# T1_Data_Top_Level.net
KiCad netlist of a schematic drawn in Altium Designer
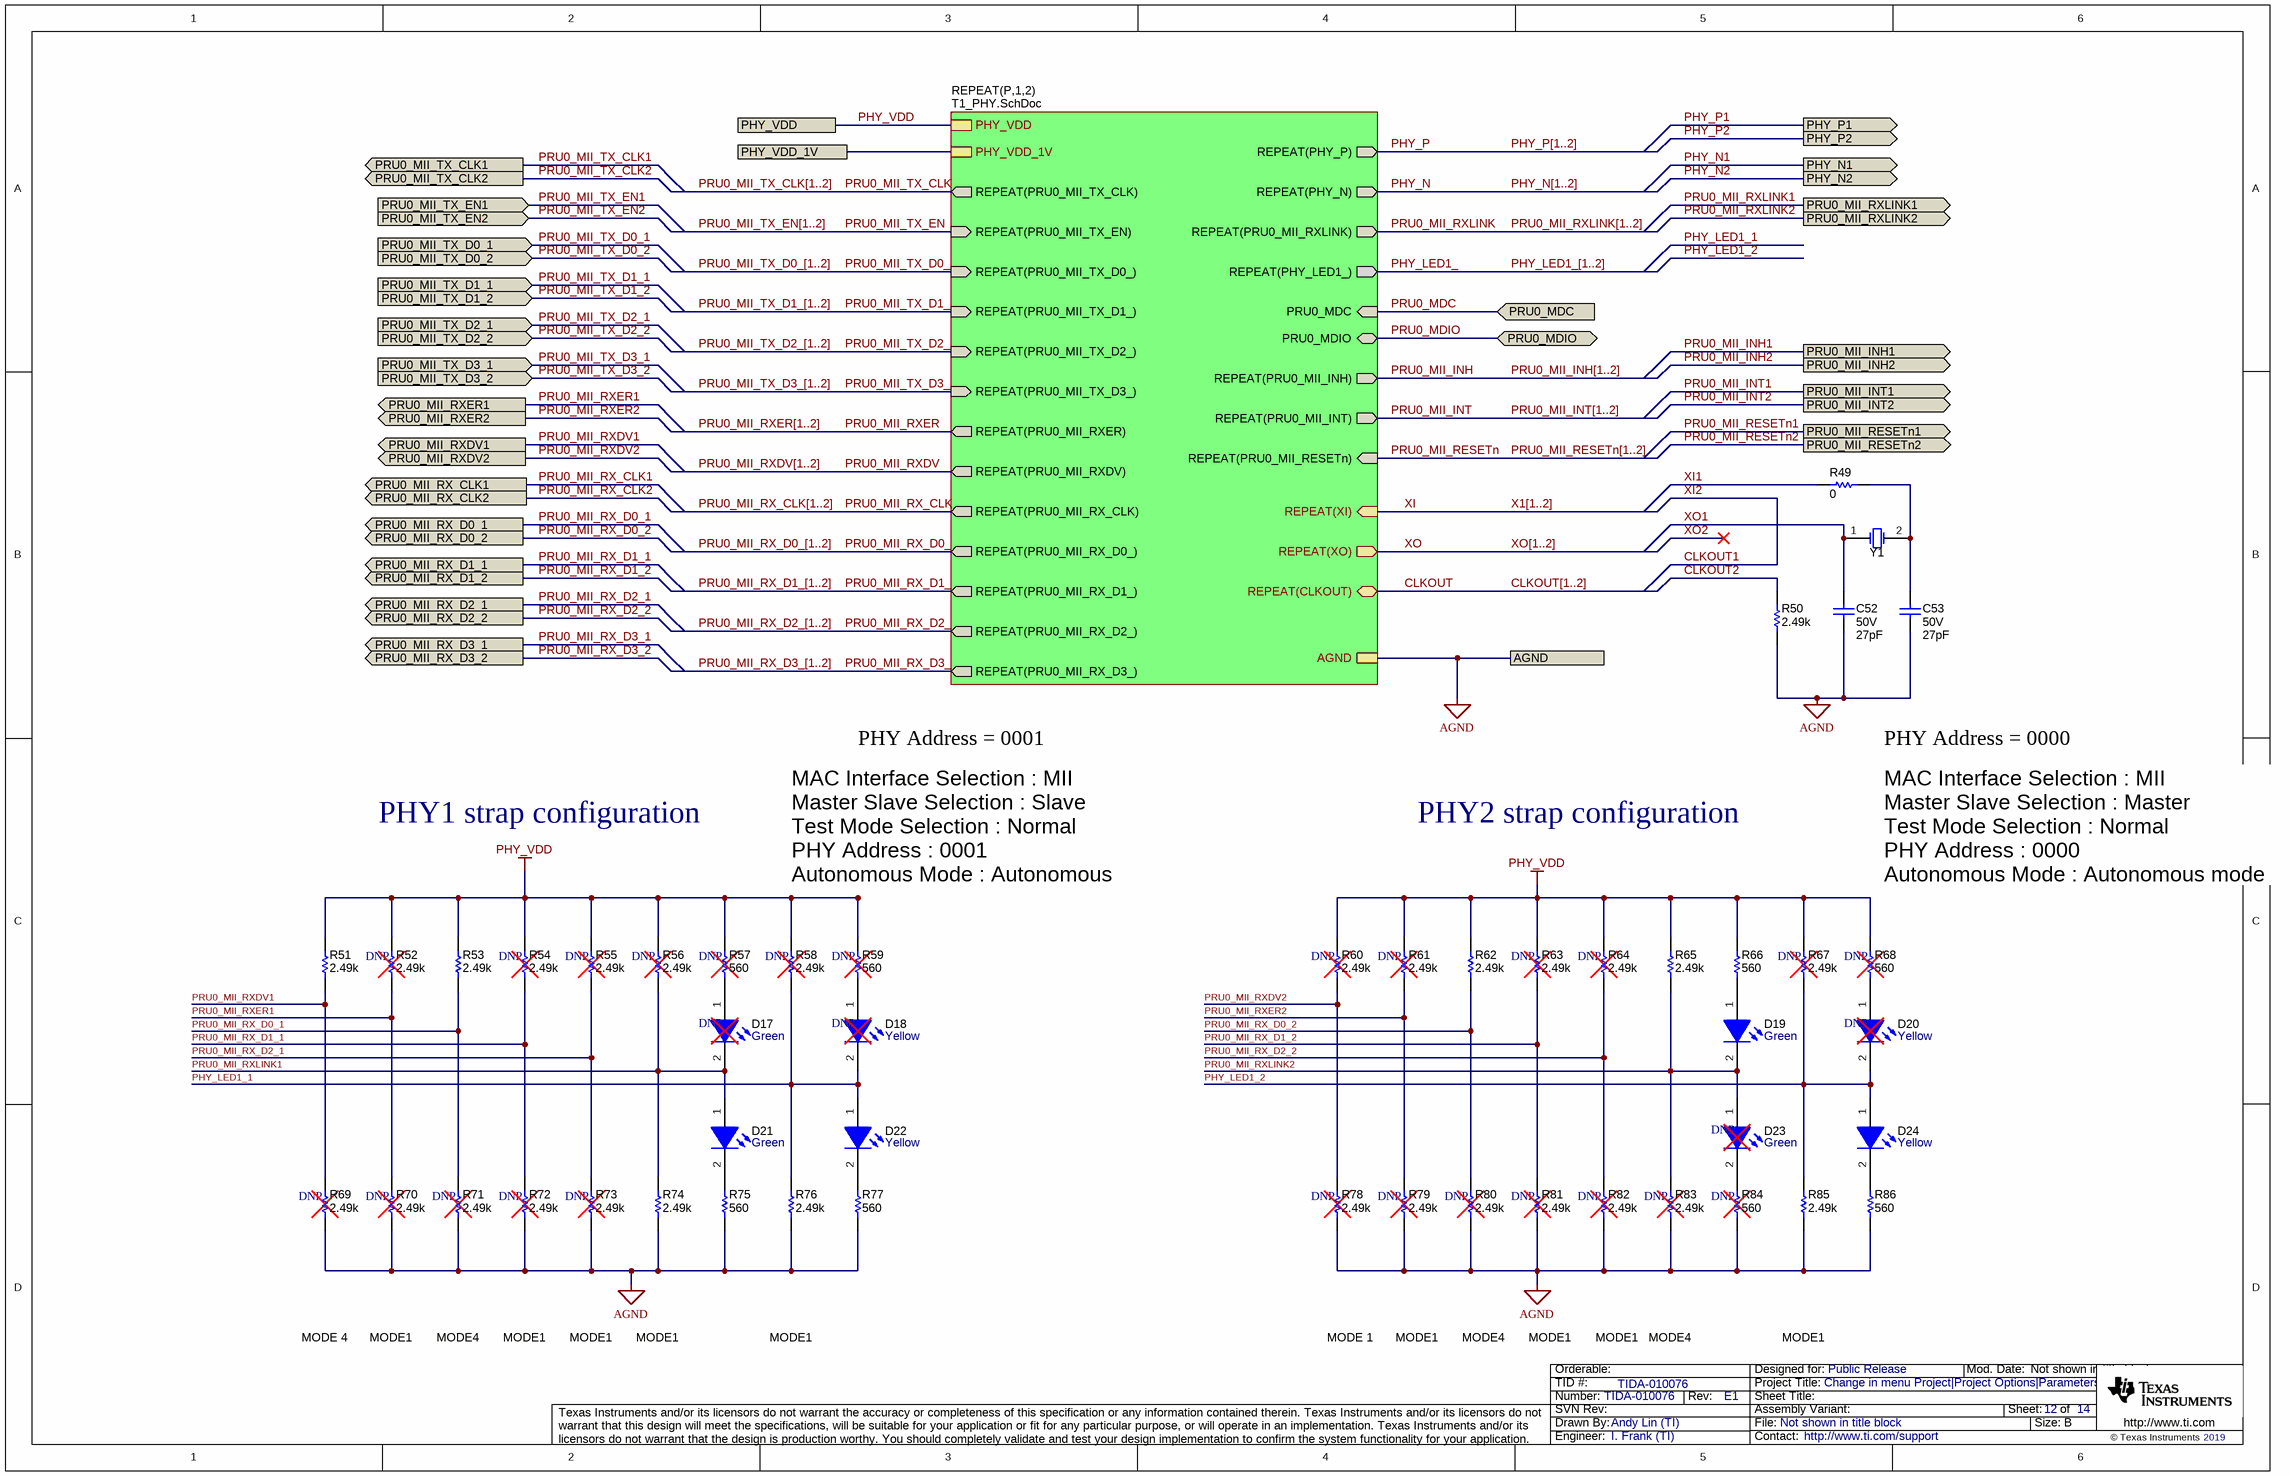
[diagram p0: T1_Data_Top_Level.SchDoc]

(export (version "E")
  (design (tool "Eeschema 10.0.6"))
  (components
    (comp (ref "C52")
      (value "GRM1885C1H270JA01D")
      (footprint "0603")
      (description "CAP, CERM, 27 pF, 50 V, +/- 5%, C0G/NP0, 0603")
      (fields
        (field (name "MANUFACTURER") "MuRata")
        (field (name "VDC_V") "50V")
        (field (name "VALUEDISPLAYED") "27pF")
        (field (name "PUBLISHER") "Texas Instruments")
      )
      (libsource (lib "Altium Vault - TI") (part "Capacitor"))
    )
    (comp (ref "C53")
      (value "GRM1885C1H270JA01D")
      (footprint "0603")
      (description "CAP, CERM, 27 pF, 50 V, +/- 5%, C0G/NP0, 0603")
      (fields
        (field (name "MANUFACTURER") "MuRata")
        (field (name "VDC_V") "50V")
        (field (name "VALUEDISPLAYED") "27pF")
        (field (name "PUBLISHER") "Texas Instruments")
      )
      (libsource (lib "Altium Vault - TI") (part "Capacitor"))
    )
    (comp (ref "D17")
      (value "Green")
      (footprint "LG L29K_GREEN")
      (description "LED, Green, SMD")
      (fields (field (name "MANUFACTURER") "OSRAM") (field (name "PARTNUMBER") "LG L29K-G2J1-24-Z"))
      (libsource (lib "Altium Vault - TI") (part "LED"))
    )
    (comp (ref "D18")
      (value "Yellow")
      (footprint "LY L29K_Yellow")
      (description "LED, Yellow, SMD")
      (fields (field (name "PARTNUMBER") "LY L29K-J1K2-26-Z") (field (name "MANUFACTURER") "OSRAM"))
      (libsource (lib "Altium Vault - TI") (part "LED"))
    )
    (comp (ref "D19")
      (value "Green")
      (footprint "LG L29K_GREEN")
      (description "LED, Green, SMD")
      (fields (field (name "MANUFACTURER") "OSRAM") (field (name "PARTNUMBER") "LG L29K-G2J1-24-Z"))
      (libsource (lib "Altium Vault - TI") (part "LED"))
    )
    (comp (ref "D20")
      (value "Yellow")
      (footprint "LY L29K_Yellow")
      (description "LED, Yellow, SMD")
      (fields (field (name "PARTNUMBER") "LY L29K-J1K2-26-Z") (field (name "MANUFACTURER") "OSRAM"))
      (libsource (lib "Altium Vault - TI") (part "LED"))
    )
    (comp (ref "D21")
      (value "Green")
      (footprint "LG L29K_GREEN")
      (description "LED, Green, SMD")
      (fields (field (name "MANUFACTURER") "OSRAM") (field (name "PARTNUMBER") "LG L29K-G2J1-24-Z"))
      (libsource (lib "Altium Vault - TI") (part "LED"))
    )
    (comp (ref "D22")
      (value "Yellow")
      (footprint "LY L29K_Yellow")
      (description "LED, Yellow, SMD")
      (fields (field (name "PARTNUMBER") "LY L29K-J1K2-26-Z") (field (name "MANUFACTURER") "OSRAM"))
      (libsource (lib "Altium Vault - TI") (part "LED"))
    )
    (comp (ref "D23")
      (value "Green")
      (footprint "LG L29K_GREEN")
      (description "LED, Green, SMD")
      (fields (field (name "MANUFACTURER") "OSRAM") (field (name "PARTNUMBER") "LG L29K-G2J1-24-Z"))
      (libsource (lib "Altium Vault - TI") (part "LED"))
    )
    (comp (ref "D24")
      (value "Yellow")
      (footprint "LY L29K_Yellow")
      (description "LED, Yellow, SMD")
      (fields (field (name "PARTNUMBER") "LY L29K-J1K2-26-Z") (field (name "MANUFACTURER") "OSRAM"))
      (libsource (lib "Altium Vault - TI") (part "LED"))
    )
    (comp (ref "R49")
      (value "CRCW04020000Z0ED")
      (footprint "0402")
      (description "RES, 0, 5%, 0.063 W, 0402")
      (fields
        (field (name "MANUFACTURER") "Vishay-Dale")
        (field (name "VALUEDISPLAYED") "0")
        (field (name "PUBLISHER") "Texas Instruments")
      )
      (libsource (lib "Altium Vault - TI") (part "Resistor"))
    )
    (comp (ref "R50")
      (value "CRCW04022K49FKED")
      (footprint "0402")
      (description "RES, 2.49 k, 1%, 0.063 W, AEC-Q200 Grade 0, 0402")
      (fields (field (name "MANUFACTURER") "Vishay-Dale") (field (name "VALUEDISPLAYED") "2.49k"))
      (libsource (lib "Altium Vault - TI") (part "Resistor"))
    )
    (comp (ref "R51")
      (value "CRCW04022K49FKED")
      (footprint "0402")
      (description "RES, 2.49 k, 1%, 0.063 W, AEC-Q200 Grade 0, 0402")
      (fields (field (name "MANUFACTURER") "Vishay-Dale") (field (name "VALUEDISPLAYED") "2.49k"))
      (libsource (lib "Altium Vault - TI") (part "Resistor"))
    )
    (comp (ref "R52")
      (value "CRCW04022K49FKED")
      (footprint "0402")
      (description "RES, 2.49 k, 1%, 0.063 W, AEC-Q200 Grade 0, 0402")
      (fields (field (name "MANUFACTURER") "Vishay-Dale") (field (name "VALUEDISPLAYED") "2.49k"))
      (libsource (lib "Altium Vault - TI") (part "Resistor"))
    )
    (comp (ref "R53")
      (value "CRCW04022K49FKED")
      (footprint "0402")
      (description "RES, 2.49 k, 1%, 0.063 W, AEC-Q200 Grade 0, 0402")
      (fields (field (name "MANUFACTURER") "Vishay-Dale") (field (name "VALUEDISPLAYED") "2.49k"))
      (libsource (lib "Altium Vault - TI") (part "Resistor"))
    )
    (comp (ref "R54")
      (value "CRCW04022K49FKED")
      (footprint "0402")
      (description "RES, 2.49 k, 1%, 0.063 W, AEC-Q200 Grade 0, 0402")
      (fields (field (name "MANUFACTURER") "Vishay-Dale") (field (name "VALUEDISPLAYED") "2.49k"))
      (libsource (lib "Altium Vault - TI") (part "Resistor"))
    )
    (comp (ref "R55")
      (value "CRCW04022K49FKED")
      (footprint "0402")
      (description "RES, 2.49 k, 1%, 0.063 W, AEC-Q200 Grade 0, 0402")
      (fields (field (name "MANUFACTURER") "Vishay-Dale") (field (name "VALUEDISPLAYED") "2.49k"))
      (libsource (lib "Altium Vault - TI") (part "Resistor"))
    )
    (comp (ref "R56")
      (value "CRCW04022K49FKED")
      (footprint "0402")
      (description "RES, 2.49 k, 1%, 0.063 W, AEC-Q200 Grade 0, 0402")
      (fields (field (name "MANUFACTURER") "Vishay-Dale") (field (name "VALUEDISPLAYED") "2.49k"))
      (libsource (lib "Altium Vault - TI") (part "Resistor"))
    )
    (comp (ref "R57")
      (value "CRCW0402560RJNED")
      (footprint "0402")
      (description "RES, 560, 5%, 0.063 W, AEC-Q200 Grade 0, 0402")
      (fields (field (name "MANUFACTURER") "Vishay-Dale") (field (name "VALUEDISPLAYED") "560"))
      (libsource (lib "Altium Vault - TI") (part "Resistor"))
    )
    (comp (ref "R58")
      (value "CRCW04022K49FKED")
      (footprint "0402")
      (description "RES, 2.49 k, 1%, 0.063 W, AEC-Q200 Grade 0, 0402")
      (fields (field (name "MANUFACTURER") "Vishay-Dale") (field (name "VALUEDISPLAYED") "2.49k"))
      (libsource (lib "Altium Vault - TI") (part "Resistor"))
    )
    (comp (ref "R59")
      (value "CRCW0402560RJNED")
      (footprint "0402")
      (description "RES, 560, 5%, 0.063 W, AEC-Q200 Grade 0, 0402")
      (fields (field (name "MANUFACTURER") "Vishay-Dale") (field (name "VALUEDISPLAYED") "560"))
      (libsource (lib "Altium Vault - TI") (part "Resistor"))
    )
    (comp (ref "R60")
      (value "CRCW04022K49FKED")
      (footprint "0402")
      (description "RES, 2.49 k, 1%, 0.063 W, AEC-Q200 Grade 0, 0402")
      (fields (field (name "MANUFACTURER") "Vishay-Dale") (field (name "VALUEDISPLAYED") "2.49k"))
      (libsource (lib "Altium Vault - TI") (part "Resistor"))
    )
    (comp (ref "R61")
      (value "CRCW04022K49FKED")
      (footprint "0402")
      (description "RES, 2.49 k, 1%, 0.063 W, AEC-Q200 Grade 0, 0402")
      (fields (field (name "MANUFACTURER") "Vishay-Dale") (field (name "VALUEDISPLAYED") "2.49k"))
      (libsource (lib "Altium Vault - TI") (part "Resistor"))
    )
    (comp (ref "R62")
      (value "CRCW04022K49FKED")
      (footprint "0402")
      (description "RES, 2.49 k, 1%, 0.063 W, AEC-Q200 Grade 0, 0402")
      (fields (field (name "MANUFACTURER") "Vishay-Dale") (field (name "VALUEDISPLAYED") "2.49k"))
      (libsource (lib "Altium Vault - TI") (part "Resistor"))
    )
    (comp (ref "R63")
      (value "CRCW04022K49FKED")
      (footprint "0402")
      (description "RES, 2.49 k, 1%, 0.063 W, AEC-Q200 Grade 0, 0402")
      (fields (field (name "MANUFACTURER") "Vishay-Dale") (field (name "VALUEDISPLAYED") "2.49k"))
      (libsource (lib "Altium Vault - TI") (part "Resistor"))
    )
    (comp (ref "R64")
      (value "CRCW04022K49FKED")
      (footprint "0402")
      (description "RES, 2.49 k, 1%, 0.063 W, AEC-Q200 Grade 0, 0402")
      (fields (field (name "MANUFACTURER") "Vishay-Dale") (field (name "VALUEDISPLAYED") "2.49k"))
      (libsource (lib "Altium Vault - TI") (part "Resistor"))
    )
    (comp (ref "R65")
      (value "CRCW04022K49FKED")
      (footprint "0402")
      (description "RES, 2.49 k, 1%, 0.063 W, AEC-Q200 Grade 0, 0402")
      (fields (field (name "MANUFACTURER") "Vishay-Dale") (field (name "VALUEDISPLAYED") "2.49k"))
      (libsource (lib "Altium Vault - TI") (part "Resistor"))
    )
    (comp (ref "R66")
      (value "CRCW0402560RJNED")
      (footprint "0402")
      (description "RES, 560, 5%, 0.063 W, AEC-Q200 Grade 0, 0402")
      (fields (field (name "MANUFACTURER") "Vishay-Dale") (field (name "VALUEDISPLAYED") "560"))
      (libsource (lib "Altium Vault - TI") (part "Resistor"))
    )
    (comp (ref "R67")
      (value "CRCW04022K49FKED")
      (footprint "0402")
      (description "RES, 2.49 k, 1%, 0.063 W, AEC-Q200 Grade 0, 0402")
      (fields (field (name "MANUFACTURER") "Vishay-Dale") (field (name "VALUEDISPLAYED") "2.49k"))
      (libsource (lib "Altium Vault - TI") (part "Resistor"))
    )
    (comp (ref "R68")
      (value "CRCW0402560RJNED")
      (footprint "0402")
      (description "RES, 560, 5%, 0.063 W, AEC-Q200 Grade 0, 0402")
      (fields (field (name "MANUFACTURER") "Vishay-Dale") (field (name "VALUEDISPLAYED") "560"))
      (libsource (lib "Altium Vault - TI") (part "Resistor"))
    )
    (comp (ref "R69")
      (value "CRCW04022K49FKED")
      (footprint "0402")
      (description "RES, 2.49 k, 1%, 0.063 W, AEC-Q200 Grade 0, 0402")
      (fields (field (name "MANUFACTURER") "Vishay-Dale") (field (name "VALUEDISPLAYED") "2.49k"))
      (libsource (lib "Altium Vault - TI") (part "Resistor"))
    )
    (comp (ref "R70")
      (value "CRCW04022K49FKED")
      (footprint "0402")
      (description "RES, 2.49 k, 1%, 0.063 W, AEC-Q200 Grade 0, 0402")
      (fields (field (name "MANUFACTURER") "Vishay-Dale") (field (name "VALUEDISPLAYED") "2.49k"))
      (libsource (lib "Altium Vault - TI") (part "Resistor"))
    )
    (comp (ref "R71")
      (value "CRCW04022K49FKED")
      (footprint "0402")
      (description "RES, 2.49 k, 1%, 0.063 W, AEC-Q200 Grade 0, 0402")
      (fields (field (name "MANUFACTURER") "Vishay-Dale") (field (name "VALUEDISPLAYED") "2.49k"))
      (libsource (lib "Altium Vault - TI") (part "Resistor"))
    )
    (comp (ref "R72")
      (value "CRCW04022K49FKED")
      (footprint "0402")
      (description "RES, 2.49 k, 1%, 0.063 W, AEC-Q200 Grade 0, 0402")
      (fields (field (name "MANUFACTURER") "Vishay-Dale") (field (name "VALUEDISPLAYED") "2.49k"))
      (libsource (lib "Altium Vault - TI") (part "Resistor"))
    )
    (comp (ref "R73")
      (value "CRCW04022K49FKED")
      (footprint "0402")
      (description "RES, 2.49 k, 1%, 0.063 W, AEC-Q200 Grade 0, 0402")
      (fields (field (name "MANUFACTURER") "Vishay-Dale") (field (name "VALUEDISPLAYED") "2.49k"))
      (libsource (lib "Altium Vault - TI") (part "Resistor"))
    )
    (comp (ref "R74")
      (value "CRCW04022K49FKED")
      (footprint "0402")
      (description "RES, 2.49 k, 1%, 0.063 W, AEC-Q200 Grade 0, 0402")
      (fields (field (name "MANUFACTURER") "Vishay-Dale") (field (name "VALUEDISPLAYED") "2.49k"))
      (libsource (lib "Altium Vault - TI") (part "Resistor"))
    )
    (comp (ref "R75")
      (value "CRCW0402560RJNED")
      (footprint "0402")
      (description "RES, 560, 5%, 0.063 W, AEC-Q200 Grade 0, 0402")
      (fields (field (name "MANUFACTURER") "Vishay-Dale") (field (name "VALUEDISPLAYED") "560"))
      (libsource (lib "Altium Vault - TI") (part "Resistor"))
    )
    (comp (ref "R76")
      (value "CRCW04022K49FKED")
      (footprint "0402")
      (description "RES, 2.49 k, 1%, 0.063 W, AEC-Q200 Grade 0, 0402")
      (fields (field (name "MANUFACTURER") "Vishay-Dale") (field (name "VALUEDISPLAYED") "2.49k"))
      (libsource (lib "Altium Vault - TI") (part "Resistor"))
    )
    (comp (ref "R77")
      (value "CRCW0402560RJNED")
      (footprint "0402")
      (description "RES, 560, 5%, 0.063 W, AEC-Q200 Grade 0, 0402")
      (fields (field (name "MANUFACTURER") "Vishay-Dale") (field (name "VALUEDISPLAYED") "560"))
      (libsource (lib "Altium Vault - TI") (part "Resistor"))
    )
    (comp (ref "R78")
      (value "CRCW04022K49FKED")
      (footprint "0402")
      (description "RES, 2.49 k, 1%, 0.063 W, AEC-Q200 Grade 0, 0402")
      (fields (field (name "MANUFACTURER") "Vishay-Dale") (field (name "VALUEDISPLAYED") "2.49k"))
      (libsource (lib "Altium Vault - TI") (part "Resistor"))
    )
    (comp (ref "R79")
      (value "CRCW04022K49FKED")
      (footprint "0402")
      (description "RES, 2.49 k, 1%, 0.063 W, AEC-Q200 Grade 0, 0402")
      (fields (field (name "MANUFACTURER") "Vishay-Dale") (field (name "VALUEDISPLAYED") "2.49k"))
      (libsource (lib "Altium Vault - TI") (part "Resistor"))
    )
    (comp (ref "R80")
      (value "CRCW04022K49FKED")
      (footprint "0402")
      (description "RES, 2.49 k, 1%, 0.063 W, AEC-Q200 Grade 0, 0402")
      (fields (field (name "MANUFACTURER") "Vishay-Dale") (field (name "VALUEDISPLAYED") "2.49k"))
      (libsource (lib "Altium Vault - TI") (part "Resistor"))
    )
    (comp (ref "R81")
      (value "CRCW04022K49FKED")
      (footprint "0402")
      (description "RES, 2.49 k, 1%, 0.063 W, AEC-Q200 Grade 0, 0402")
      (fields (field (name "MANUFACTURER") "Vishay-Dale") (field (name "VALUEDISPLAYED") "2.49k"))
      (libsource (lib "Altium Vault - TI") (part "Resistor"))
    )
    (comp (ref "R82")
      (value "CRCW04022K49FKED")
      (footprint "0402")
      (description "RES, 2.49 k, 1%, 0.063 W, AEC-Q200 Grade 0, 0402")
      (fields (field (name "MANUFACTURER") "Vishay-Dale") (field (name "VALUEDISPLAYED") "2.49k"))
      (libsource (lib "Altium Vault - TI") (part "Resistor"))
    )
    (comp (ref "R83")
      (value "CRCW04022K49FKED")
      (footprint "0402")
      (description "RES, 2.49 k, 1%, 0.063 W, AEC-Q200 Grade 0, 0402")
      (fields (field (name "MANUFACTURER") "Vishay-Dale") (field (name "VALUEDISPLAYED") "2.49k"))
      (libsource (lib "Altium Vault - TI") (part "Resistor"))
    )
    (comp (ref "R84")
      (value "CRCW0402560RJNED")
      (footprint "0402")
      (description "RES, 560, 5%, 0.063 W, AEC-Q200 Grade 0, 0402")
      (fields (field (name "MANUFACTURER") "Vishay-Dale") (field (name "VALUEDISPLAYED") "560"))
      (libsource (lib "Altium Vault - TI") (part "Resistor"))
    )
    (comp (ref "R85")
      (value "CRCW04022K49FKED")
      (footprint "0402")
      (description "RES, 2.49 k, 1%, 0.063 W, AEC-Q200 Grade 0, 0402")
      (fields (field (name "MANUFACTURER") "Vishay-Dale") (field (name "VALUEDISPLAYED") "2.49k"))
      (libsource (lib "Altium Vault - TI") (part "Resistor"))
    )
    (comp (ref "R86")
      (value "CRCW0402560RJNED")
      (footprint "0402")
      (description "RES, 560, 5%, 0.063 W, AEC-Q200 Grade 0, 0402")
      (fields (field (name "MANUFACTURER") "Vishay-Dale") (field (name "VALUEDISPLAYED") "560"))
      (libsource (lib "Altium Vault - TI") (part "Resistor"))
    )
    (comp (ref "Y1")
      (value "ABM3-25.000MHZ-D2Y-T")
      (footprint "XTAL_ABM3")
      (description "Crystal, 25 MHz, 18 pF, SMD")
      (fields (field (name "MANUFACTURER") "Abracon Corporation"))
      (libsource (lib "Altium Vault - TI") (part "Xtal"))
    )
  )
  (nets
    (net (code "5") (name "/CLKOUT2") (class "Default")
      (node (ref "R50") (pin "2") (pinfunction "2_2") (pintype "passive"))
    )
    (net (code "10") (name "/PHY_LED1_1") (class "Default")
      (node (ref "D18") (pin "2") (pinfunction "K_2") (pintype "passive"))
      (node (ref "D22") (pin "1") (pinfunction "A_1") (pintype "passive"))
      (node (ref "R58") (pin "1") (pinfunction "1_1") (pintype "passive"))
      (node (ref "R76") (pin "2") (pinfunction "2_2") (pintype "passive"))
    )
    (net (code "11") (name "/PHY_LED1_2") (class "Default")
      (node (ref "D20") (pin "2") (pinfunction "K_2") (pintype "passive"))
      (node (ref "D24") (pin "1") (pinfunction "A_1") (pintype "passive"))
      (node (ref "R67") (pin "1") (pinfunction "1_1") (pintype "passive"))
      (node (ref "R85") (pin "2") (pinfunction "2_2") (pintype "passive"))
    )
    (net (code "37") (name "/PRU0_MII_RXDV1") (class "Default")
      (node (ref "R51") (pin "1") (pinfunction "1_1") (pintype "passive"))
      (node (ref "R69") (pin "2") (pinfunction "2_2") (pintype "passive"))
    )
    (net (code "38") (name "/PRU0_MII_RXDV2") (class "Default")
      (node (ref "R60") (pin "1") (pinfunction "1_1") (pintype "passive"))
      (node (ref "R78") (pin "2") (pinfunction "2_2") (pintype "passive"))
    )
    (net (code "41") (name "/PRU0_MII_RXER1") (class "Default")
      (node (ref "R52") (pin "1") (pinfunction "1_1") (pintype "passive"))
      (node (ref "R70") (pin "2") (pinfunction "2_2") (pintype "passive"))
    )
    (net (code "42") (name "/PRU0_MII_RXER2") (class "Default")
      (node (ref "R61") (pin "1") (pinfunction "1_1") (pintype "passive"))
      (node (ref "R79") (pin "2") (pinfunction "2_2") (pintype "passive"))
    )
    (net (code "45") (name "/PRU0_MII_RXLINK1") (class "Default")
      (node (ref "D17") (pin "2") (pinfunction "K_2") (pintype "passive"))
      (node (ref "D21") (pin "1") (pinfunction "A_1") (pintype "passive"))
      (node (ref "R56") (pin "1") (pinfunction "1_1") (pintype "passive"))
      (node (ref "R74") (pin "2") (pinfunction "2_2") (pintype "passive"))
    )
    (net (code "46") (name "/PRU0_MII_RXLINK2") (class "Default")
      (node (ref "D19") (pin "2") (pinfunction "K_2") (pintype "passive"))
      (node (ref "D23") (pin "1") (pinfunction "A_1") (pintype "passive"))
      (node (ref "R65") (pin "1") (pinfunction "1_1") (pintype "passive"))
      (node (ref "R83") (pin "2") (pinfunction "2_2") (pintype "passive"))
    )
    (net (code "53") (name "/PRU0_MII_RX_D0_1") (class "Default")
      (node (ref "R53") (pin "1") (pinfunction "1_1") (pintype "passive"))
      (node (ref "R71") (pin "2") (pinfunction "2_2") (pintype "passive"))
    )
    (net (code "54") (name "/PRU0_MII_RX_D0_2") (class "Default")
      (node (ref "R62") (pin "1") (pinfunction "1_1") (pintype "passive"))
      (node (ref "R80") (pin "2") (pinfunction "2_2") (pintype "passive"))
    )
    (net (code "57") (name "/PRU0_MII_RX_D1_1") (class "Default")
      (node (ref "R54") (pin "1") (pinfunction "1_1") (pintype "passive"))
      (node (ref "R72") (pin "2") (pinfunction "2_2") (pintype "passive"))
    )
    (net (code "58") (name "/PRU0_MII_RX_D1_2") (class "Default")
      (node (ref "R63") (pin "1") (pinfunction "1_1") (pintype "passive"))
      (node (ref "R81") (pin "2") (pinfunction "2_2") (pintype "passive"))
    )
    (net (code "61") (name "/PRU0_MII_RX_D2_1") (class "Default")
      (node (ref "R55") (pin "1") (pinfunction "1_1") (pintype "passive"))
      (node (ref "R73") (pin "2") (pinfunction "2_2") (pintype "passive"))
    )
    (net (code "62") (name "/PRU0_MII_RX_D2_2") (class "Default")
      (node (ref "R64") (pin "1") (pinfunction "1_1") (pintype "passive"))
      (node (ref "R82") (pin "2") (pinfunction "2_2") (pintype "passive"))
    )
    (net (code "94") (name "/XI1") (class "Default")
      (node (ref "R49") (pin "1") (pinfunction "1_1") (pintype "passive"))
    )
    (net (code "96") (name "/XO1") (class "Default")
      (node (ref "C52") (pin "1") (pinfunction "1_1") (pintype "passive"))
      (node (ref "Y1") (pin "1") (pinfunction "OSC1_1") (pintype "passive"))
    )
    (net (code "99") (name "AGND") (class "Default")
      (node (ref "C52") (pin "2") (pinfunction "2_2") (pintype "passive"))
      (node (ref "C53") (pin "2") (pinfunction "2_2") (pintype "passive"))
      (node (ref "R50") (pin "1") (pinfunction "1_1") (pintype "passive"))
      (node (ref "R69") (pin "1") (pinfunction "1_1") (pintype "passive"))
      (node (ref "R70") (pin "1") (pinfunction "1_1") (pintype "passive"))
      (node (ref "R71") (pin "1") (pinfunction "1_1") (pintype "passive"))
      (node (ref "R72") (pin "1") (pinfunction "1_1") (pintype "passive"))
      (node (ref "R73") (pin "1") (pinfunction "1_1") (pintype "passive"))
      (node (ref "R74") (pin "1") (pinfunction "1_1") (pintype "passive"))
      (node (ref "R75") (pin "1") (pinfunction "1_1") (pintype "passive"))
      (node (ref "R76") (pin "1") (pinfunction "1_1") (pintype "passive"))
      (node (ref "R77") (pin "1") (pinfunction "1_1") (pintype "passive"))
      (node (ref "R78") (pin "1") (pinfunction "1_1") (pintype "passive"))
      (node (ref "R79") (pin "1") (pinfunction "1_1") (pintype "passive"))
      (node (ref "R80") (pin "1") (pinfunction "1_1") (pintype "passive"))
      (node (ref "R81") (pin "1") (pinfunction "1_1") (pintype "passive"))
      (node (ref "R82") (pin "1") (pinfunction "1_1") (pintype "passive"))
      (node (ref "R83") (pin "1") (pinfunction "1_1") (pintype "passive"))
      (node (ref "R84") (pin "1") (pinfunction "1_1") (pintype "passive"))
      (node (ref "R85") (pin "1") (pinfunction "1_1") (pintype "passive"))
      (node (ref "R86") (pin "1") (pinfunction "1_1") (pintype "passive"))
    )
    (net (code "100") (name "Net-(D17-A)") (class "Default")
      (node (ref "D17") (pin "1") (pinfunction "A_1") (pintype "passive"))
      (node (ref "R57") (pin "1") (pinfunction "1_1") (pintype "passive"))
    )
    (net (code "101") (name "Net-(D18-A)") (class "Default")
      (node (ref "D18") (pin "1") (pinfunction "A_1") (pintype "passive"))
      (node (ref "R59") (pin "1") (pinfunction "1_1") (pintype "passive"))
    )
    (net (code "102") (name "Net-(D19-A)") (class "Default")
      (node (ref "D19") (pin "1") (pinfunction "A_1") (pintype "passive"))
      (node (ref "R66") (pin "1") (pinfunction "1_1") (pintype "passive"))
    )
    (net (code "103") (name "Net-(D20-A)") (class "Default")
      (node (ref "D20") (pin "1") (pinfunction "A_1") (pintype "passive"))
      (node (ref "R68") (pin "1") (pinfunction "1_1") (pintype "passive"))
    )
    (net (code "104") (name "Net-(D21-K)") (class "Default")
      (node (ref "D21") (pin "2") (pinfunction "K_2") (pintype "passive"))
      (node (ref "R75") (pin "2") (pinfunction "2_2") (pintype "passive"))
    )
    (net (code "105") (name "Net-(D22-K)") (class "Default")
      (node (ref "D22") (pin "2") (pinfunction "K_2") (pintype "passive"))
      (node (ref "R77") (pin "2") (pinfunction "2_2") (pintype "passive"))
    )
    (net (code "106") (name "Net-(D23-K)") (class "Default")
      (node (ref "D23") (pin "2") (pinfunction "K_2") (pintype "passive"))
      (node (ref "R84") (pin "2") (pinfunction "2_2") (pintype "passive"))
    )
    (net (code "107") (name "Net-(D24-K)") (class "Default")
      (node (ref "D24") (pin "2") (pinfunction "K_2") (pintype "passive"))
      (node (ref "R86") (pin "2") (pinfunction "2_2") (pintype "passive"))
    )
    (net (code "108") (name "Net-(Y1-OSC2)") (class "Default")
      (node (ref "C53") (pin "1") (pinfunction "1_1") (pintype "passive"))
      (node (ref "R49") (pin "2") (pinfunction "2_2") (pintype "passive"))
      (node (ref "Y1") (pin "2") (pinfunction "OSC2_2") (pintype "passive"))
    )
    (net (code "109") (name "PHY_VDD") (class "Default")
      (node (ref "R51") (pin "2") (pinfunction "2_2") (pintype "passive"))
      (node (ref "R52") (pin "2") (pinfunction "2_2") (pintype "passive"))
      (node (ref "R53") (pin "2") (pinfunction "2_2") (pintype "passive"))
      (node (ref "R54") (pin "2") (pinfunction "2_2") (pintype "passive"))
      (node (ref "R55") (pin "2") (pinfunction "2_2") (pintype "passive"))
      (node (ref "R56") (pin "2") (pinfunction "2_2") (pintype "passive"))
      (node (ref "R57") (pin "2") (pinfunction "2_2") (pintype "passive"))
      (node (ref "R58") (pin "2") (pinfunction "2_2") (pintype "passive"))
      (node (ref "R59") (pin "2") (pinfunction "2_2") (pintype "passive"))
      (node (ref "R60") (pin "2") (pinfunction "2_2") (pintype "passive"))
      (node (ref "R61") (pin "2") (pinfunction "2_2") (pintype "passive"))
      (node (ref "R62") (pin "2") (pinfunction "2_2") (pintype "passive"))
      (node (ref "R63") (pin "2") (pinfunction "2_2") (pintype "passive"))
      (node (ref "R64") (pin "2") (pinfunction "2_2") (pintype "passive"))
      (node (ref "R65") (pin "2") (pinfunction "2_2") (pintype "passive"))
      (node (ref "R66") (pin "2") (pinfunction "2_2") (pintype "passive"))
      (node (ref "R67") (pin "2") (pinfunction "2_2") (pintype "passive"))
      (node (ref "R68") (pin "2") (pinfunction "2_2") (pintype "passive"))
    )
  )
)
